# 20130725_Wave_Clock_PIC32MX130_Mono.net
KiCad netlist of a schematic drawn in EAGLE
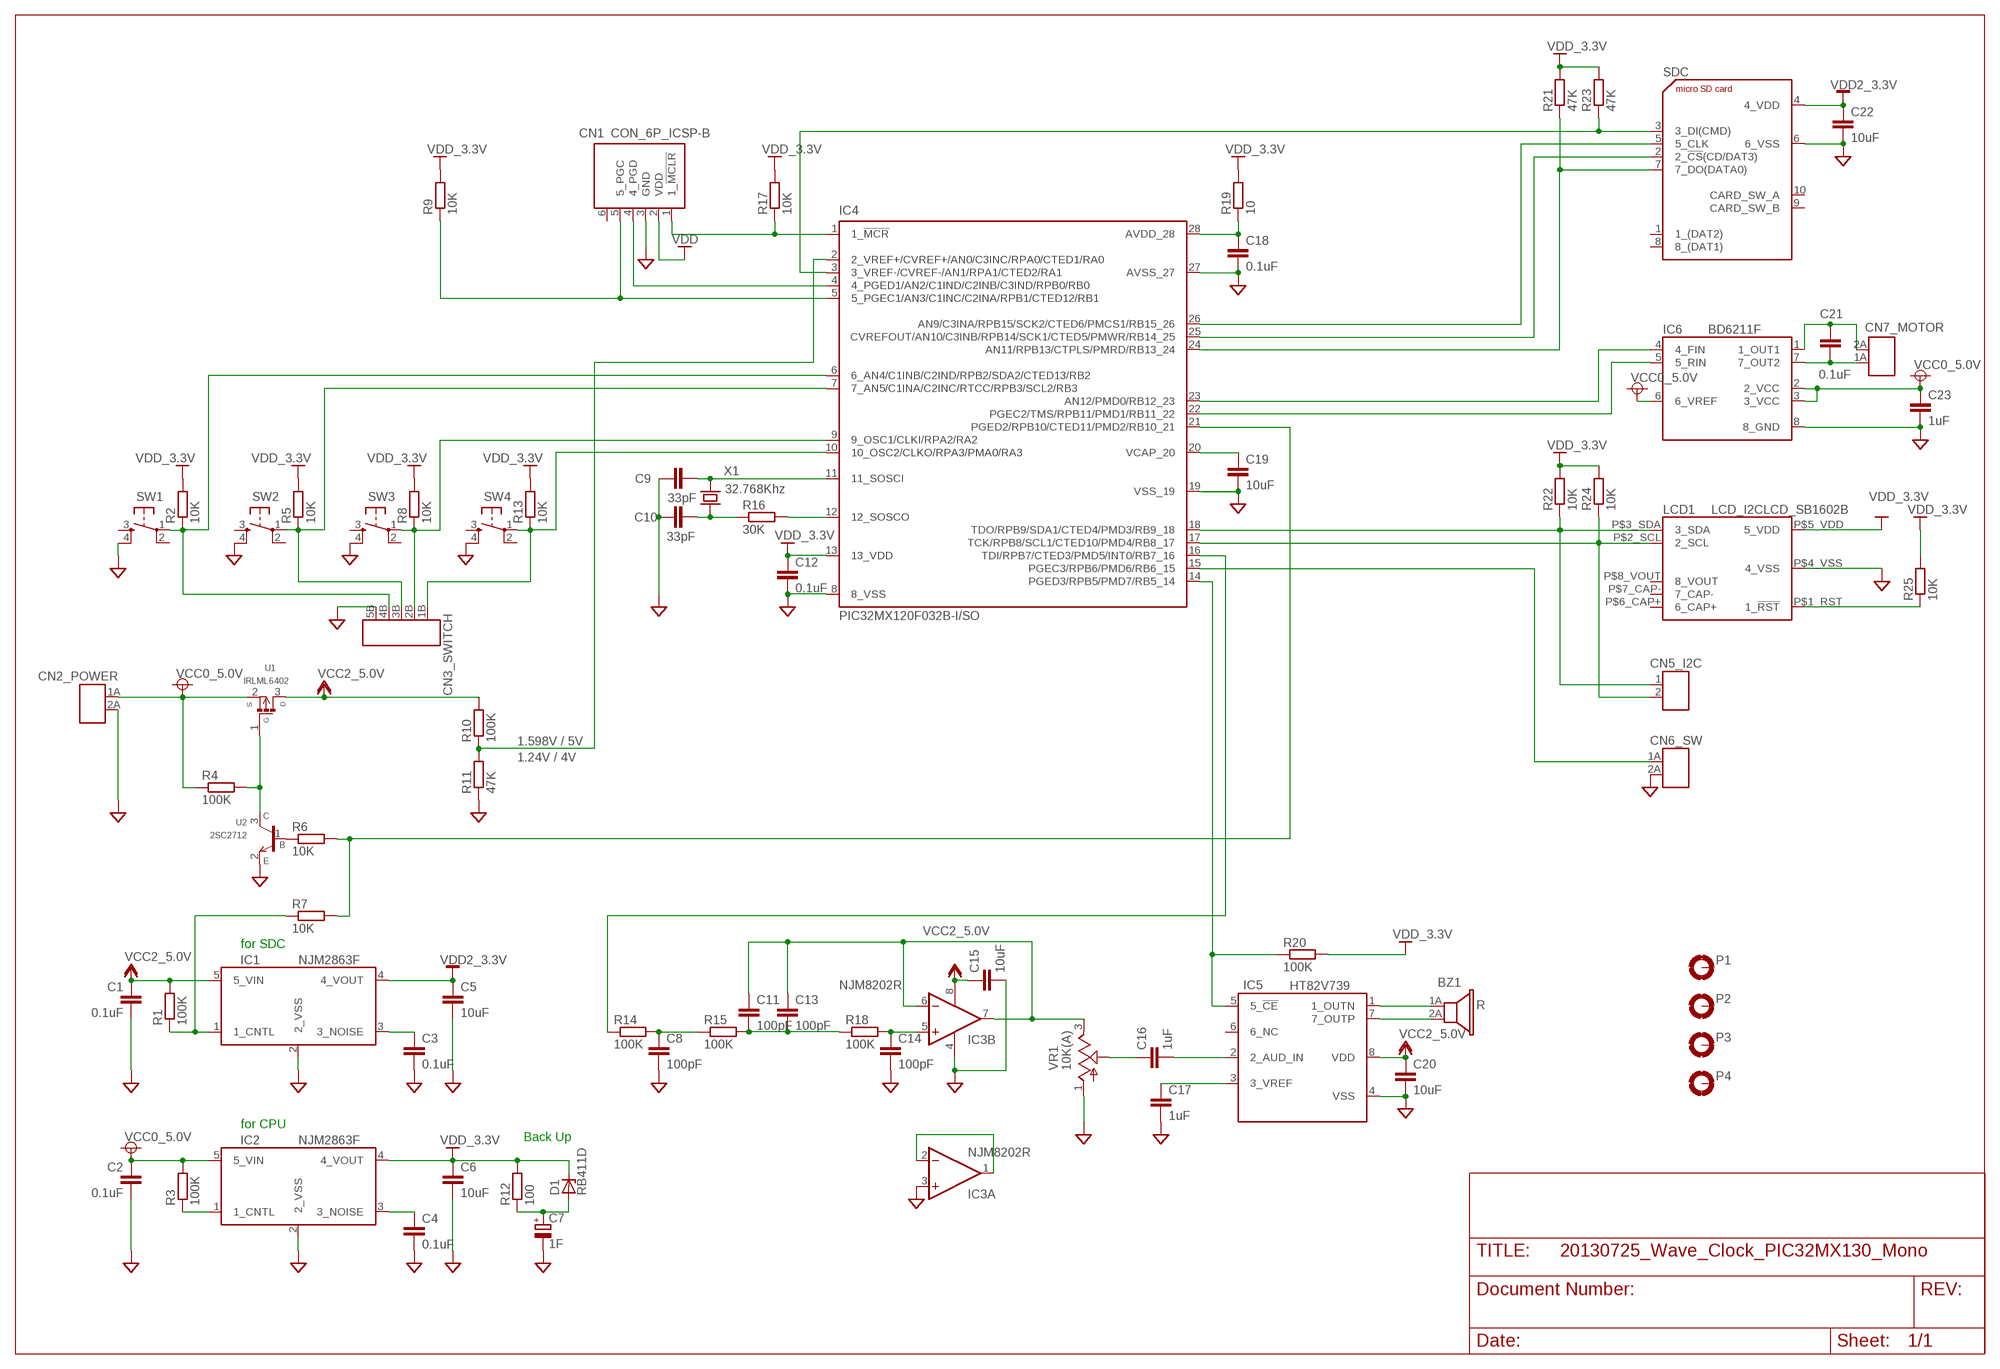
[diagram p0: schematic, sheet 1]

(export (version "E")
  (design (tool "Eeschema 10.0.6"))
  (components
    (comp (ref "BZ1")
      (value "R")
      (footprint "eagle-import:TERMINAL_AH-2P")
      (libsource (lib "eagle-import") (part "SPEAKER-H"))
    )
    (comp (ref "C1")
      (value "0.1uF")
      (footprint "eagle-import:1608")
      (libsource (lib "eagle-import") (part "C-EU2M1608"))
    )
    (comp (ref "C2")
      (value "0.1uF")
      (footprint "eagle-import:1608")
      (libsource (lib "eagle-import") (part "C-EU2M1608"))
    )
    (comp (ref "C3")
      (value "0.1uF")
      (footprint "eagle-import:1608")
      (libsource (lib "eagle-import") (part "C-EU2M1608"))
    )
    (comp (ref "C4")
      (value "0.1uF")
      (footprint "eagle-import:1608")
      (libsource (lib "eagle-import") (part "C-EU2M1608"))
    )
    (comp (ref "C5")
      (value "10uF")
      (footprint "eagle-import:3216")
      (libsource (lib "eagle-import") (part "C-EU2M3216"))
    )
    (comp (ref "C6")
      (value "10uF")
      (footprint "eagle-import:3216")
      (libsource (lib "eagle-import") (part "C-EU2M3216"))
    )
    (comp (ref "C7")
      (value "1F")
      (footprint "eagle-import:E5-19V-B")
      (libsource (lib "eagle-import") (part "CPOL-EDLC-1F5.5V-H"))
    )
    (comp (ref "C8")
      (value "100pF")
      (footprint "eagle-import:1608")
      (libsource (lib "eagle-import") (part "C-EU2M1608"))
    )
    (comp (ref "C9")
      (value "33pF")
      (footprint "eagle-import:1608")
      (libsource (lib "eagle-import") (part "C-EU2M1608"))
    )
    (comp (ref "C10")
      (value "33pF")
      (footprint "eagle-import:1608")
      (libsource (lib "eagle-import") (part "C-EU2M1608"))
    )
    (comp (ref "C11")
      (value "100pF")
      (footprint "eagle-import:1608")
      (libsource (lib "eagle-import") (part "C-EU2M1608"))
    )
    (comp (ref "C12")
      (value "0.1uF")
      (footprint "eagle-import:1608")
      (libsource (lib "eagle-import") (part "C-EU2M1608"))
    )
    (comp (ref "C13")
      (value "100pF")
      (footprint "eagle-import:1608")
      (libsource (lib "eagle-import") (part "C-EU2M1608"))
    )
    (comp (ref "C14")
      (value "100pF")
      (footprint "eagle-import:1608")
      (libsource (lib "eagle-import") (part "C-EU2M1608"))
    )
    (comp (ref "C15")
      (value "10uF")
      (footprint "eagle-import:3216")
      (libsource (lib "eagle-import") (part "C-EU2M3216"))
    )
    (comp (ref "C16")
      (value "1uF")
      (footprint "eagle-import:1608")
      (libsource (lib "eagle-import") (part "C-EU2M1608"))
    )
    (comp (ref "C17")
      (value "1uF")
      (footprint "eagle-import:1608")
      (libsource (lib "eagle-import") (part "C-EU2M1608"))
    )
    (comp (ref "C18")
      (value "0.1uF")
      (footprint "eagle-import:1608")
      (libsource (lib "eagle-import") (part "C-EU2M1608"))
    )
    (comp (ref "C19")
      (value "10uF")
      (footprint "eagle-import:3216")
      (libsource (lib "eagle-import") (part "C-EU2M3216"))
    )
    (comp (ref "C20")
      (value "10uF")
      (footprint "eagle-import:3216")
      (libsource (lib "eagle-import") (part "C-EU2M3216"))
    )
    (comp (ref "C21")
      (value "0.1uF")
      (footprint "eagle-import:1608")
      (libsource (lib "eagle-import") (part "C-EU2M1608"))
    )
    (comp (ref "C22")
      (value "10uF")
      (footprint "eagle-import:3216")
      (libsource (lib "eagle-import") (part "C-EU2M3216"))
    )
    (comp (ref "C23")
      (value "1uF")
      (footprint "eagle-import:1608")
      (libsource (lib "eagle-import") (part "C-EU2M1608"))
    )
    (comp (ref "CN1")
      (value "CON_6P_ICSP-B")
      (footprint "eagle-import:CON_DIP_6-B")
      (libsource (lib "eagle-import") (part "CON_6P_ICSP-B"))
    )
    (comp (ref "CN2_POWER")
      (value "CON_2P-B")
      (footprint "eagle-import:TERMINAL_AH-2P")
      (libsource (lib "eagle-import") (part "CON_2P-H"))
    )
    (comp (ref "CN3_SWITCH")
      (value "CON_5PVR")
      (footprint "eagle-import:TERMINAL_AV-5P")
      (libsource (lib "eagle-import") (part "CON_5PVR"))
    )
    (comp (ref "CN5_I2C")
      (value "CON_2P-B")
      (footprint "eagle-import:CON_DIP_2-B")
      (libsource (lib "eagle-import") (part "CON_2P-B"))
    )
    (comp (ref "CN6_SW")
      (value "CON_2P-B")
      (footprint "eagle-import:TERMINAL_AH-2P")
      (libsource (lib "eagle-import") (part "CON_2P-H"))
    )
    (comp (ref "CN7_MOTOR")
      (value "CON_2P-B")
      (footprint "eagle-import:TERMINAL_AH-2P")
      (libsource (lib "eagle-import") (part "CON_2P-H"))
    )
    (comp (ref "D1")
      (value "RB411D")
      (footprint "eagle-import:SOT-23-3-2915-B")
      (libsource (lib "eagle-import") (part "Z_DIODE-SC59"))
    )
    (comp (ref "IC1")
      (value "NJM2863F")
      (footprint "eagle-import:SOT-23-5-2916-B")
      (libsource (lib "eagle-import") (part "NJM2863F"))
    )
    (comp (ref "IC2")
      (value "NJM2863F")
      (footprint "eagle-import:SOT-23-5-2916-B")
      (libsource (lib "eagle-import") (part "NJM2863F"))
    )
    (comp (ref "IC3")
      (value "NJM8202R")
      (footprint "eagle-import:MSOP08")
      (libsource (lib "eagle-import") (part "NJM8202R"))
    )
    (comp (ref "IC4")
      (value "PIC32MX120F032B-I/SO")
      (footprint "eagle-import:SO28W")
      (libsource (lib "eagle-import") (part "PIC32MX120F032B-I/SO"))
    )
    (comp (ref "IC5")
      (value "HT82V739")
      (footprint "eagle-import:DIP08-B")
      (libsource (lib "eagle-import") (part "HT82V739"))
    )
    (comp (ref "IC6")
      (value "BD6211F")
      (footprint "eagle-import:SOP8")
      (libsource (lib "eagle-import") (part "BD6211F"))
    )
    (comp (ref "LCD1")
      (value "LCD_I2CLCD_SB1602B")
      (footprint "eagle-import:LCD_SB1602B")
      (libsource (lib "eagle-import") (part "LCD_I2CLCD_SB1602B"))
    )
    (comp (ref "P1")
      (value "MOUNT-PAD3.3")
      (footprint "eagle-import:PAD-3.3-B")
      (libsource (lib "eagle-import") (part "MOUNT-PAD3.3"))
    )
    (comp (ref "P2")
      (value "MOUNT-PAD3.3")
      (footprint "eagle-import:PAD-3.3-B")
      (libsource (lib "eagle-import") (part "MOUNT-PAD3.3"))
    )
    (comp (ref "P3")
      (value "MOUNT-PAD3.3")
      (footprint "eagle-import:PAD-3.3-B")
      (libsource (lib "eagle-import") (part "MOUNT-PAD3.3"))
    )
    (comp (ref "P4")
      (value "MOUNT-PAD3.3")
      (footprint "eagle-import:PAD-3.3-B")
      (libsource (lib "eagle-import") (part "MOUNT-PAD3.3"))
    )
    (comp (ref "R1")
      (value "100K")
      (footprint "eagle-import:1608")
      (libsource (lib "eagle-import") (part "R-EU2M1608"))
    )
    (comp (ref "R2")
      (value "10K")
      (footprint "eagle-import:1608")
      (libsource (lib "eagle-import") (part "R-EU2M1608"))
    )
    (comp (ref "R3")
      (value "100K")
      (footprint "eagle-import:1608")
      (libsource (lib "eagle-import") (part "R-EU2M1608"))
    )
    (comp (ref "R4")
      (value "100K")
      (footprint "eagle-import:1608")
      (libsource (lib "eagle-import") (part "R-EU2M1608"))
    )
    (comp (ref "R5")
      (value "10K")
      (footprint "eagle-import:1608")
      (libsource (lib "eagle-import") (part "R-EU2M1608"))
    )
    (comp (ref "R6")
      (value "10K")
      (footprint "eagle-import:1608")
      (libsource (lib "eagle-import") (part "R-EU2M1608"))
    )
    (comp (ref "R7")
      (value "10K")
      (footprint "eagle-import:1608")
      (libsource (lib "eagle-import") (part "R-EU2M1608"))
    )
    (comp (ref "R8")
      (value "10K")
      (footprint "eagle-import:1608")
      (libsource (lib "eagle-import") (part "R-EU2M1608"))
    )
    (comp (ref "R9")
      (value "10K")
      (footprint "eagle-import:1608")
      (libsource (lib "eagle-import") (part "R-EU2M1608"))
    )
    (comp (ref "R10")
      (value "100K")
      (footprint "eagle-import:1608")
      (libsource (lib "eagle-import") (part "R-EU2M1608"))
    )
    (comp (ref "R11")
      (value "47K")
      (footprint "eagle-import:1608")
      (libsource (lib "eagle-import") (part "R-EU2M1608"))
    )
    (comp (ref "R12")
      (value "100")
      (footprint "eagle-import:1608")
      (libsource (lib "eagle-import") (part "R-EU2M1608"))
    )
    (comp (ref "R13")
      (value "10K")
      (footprint "eagle-import:1608")
      (libsource (lib "eagle-import") (part "R-EU2M1608"))
    )
    (comp (ref "R14")
      (value "100K")
      (footprint "eagle-import:1608")
      (libsource (lib "eagle-import") (part "R-EU2M1608"))
    )
    (comp (ref "R15")
      (value "100K")
      (footprint "eagle-import:1608")
      (libsource (lib "eagle-import") (part "R-EU2M1608"))
    )
    (comp (ref "R16")
      (value "30K")
      (footprint "eagle-import:1608")
      (libsource (lib "eagle-import") (part "R-EU2M1608"))
    )
    (comp (ref "R17")
      (value "10K")
      (footprint "eagle-import:1608")
      (libsource (lib "eagle-import") (part "R-EU2M1608"))
    )
    (comp (ref "R18")
      (value "100K")
      (footprint "eagle-import:1608")
      (libsource (lib "eagle-import") (part "R-EU2M1608"))
    )
    (comp (ref "R19")
      (value "10")
      (footprint "eagle-import:1608")
      (libsource (lib "eagle-import") (part "R-EU2M1608"))
    )
    (comp (ref "R20")
      (value "100K")
      (footprint "eagle-import:1608")
      (libsource (lib "eagle-import") (part "R-EU2M1608"))
    )
    (comp (ref "R21")
      (value "47K")
      (footprint "eagle-import:1608")
      (libsource (lib "eagle-import") (part "R-EU2M1608"))
    )
    (comp (ref "R22")
      (value "10K")
      (footprint "eagle-import:1608")
      (libsource (lib "eagle-import") (part "R-EU2M1608"))
    )
    (comp (ref "R23")
      (value "47K")
      (footprint "eagle-import:1608")
      (libsource (lib "eagle-import") (part "R-EU2M1608"))
    )
    (comp (ref "R24")
      (value "10K")
      (footprint "eagle-import:1608")
      (libsource (lib "eagle-import") (part "R-EU2M1608"))
    )
    (comp (ref "R25")
      (value "10K")
      (footprint "eagle-import:1608")
      (libsource (lib "eagle-import") (part "R-EU2M1608"))
    )
    (comp (ref "SDC")
      (value "DM3AT-SF-PEJＤ")
      (footprint "eagle-import:DM3AT-SF-DIP")
      (libsource (lib "eagle-import") (part "DM3AT-SF-PEJＤ"))
    )
    (comp (ref "SW1")
      (value "SW_TACT1")
      (footprint "eagle-import:SW_TACT-B")
      (libsource (lib "eagle-import") (part "SW_TACT1"))
    )
    (comp (ref "SW2")
      (value "SW_TACT1")
      (footprint "eagle-import:SW_TACT-B")
      (libsource (lib "eagle-import") (part "SW_TACT1"))
    )
    (comp (ref "SW3")
      (value "SW_TACT1")
      (footprint "eagle-import:SW_TACT-B")
      (libsource (lib "eagle-import") (part "SW_TACT1"))
    )
    (comp (ref "SW4")
      (value "SW_TACT1")
      (footprint "eagle-import:SW_TACT-B")
      (libsource (lib "eagle-import") (part "SW_TACT1"))
    )
    (comp (ref "U1")
      (value "IRLML6402")
      (footprint "eagle-import:SC-59-2915")
      (libsource (lib "eagle-import") (part "IRLML6402"))
    )
    (comp (ref "U2")
      (value "2SC2712")
      (footprint "eagle-import:SOT-23-3-2915-B")
      (libsource (lib "eagle-import") (part "2SC2712"))
    )
    (comp (ref "VR1")
      (value "10K(A)")
      (footprint "eagle-import:VOL_MIDDLE")
      (libsource (lib "eagle-import") (part "POT-VOL"))
    )
    (comp (ref "X1")
      (value "32.768Khz")
      (footprint "eagle-import:VT-200")
      (libsource (lib "eagle-import") (part "XTALVT"))
    )
  )
  (nets
    (net (code "1") (name "GND") (class "Default")
      (node (ref "C1") (pin "2") (pinfunction "2_2") (pintype "passive"))
      (node (ref "C10") (pin "2") (pinfunction "2_2") (pintype "passive"))
      (node (ref "C12") (pin "2") (pinfunction "2_2") (pintype "passive"))
      (node (ref "C14") (pin "2") (pinfunction "2_2") (pintype "passive"))
      (node (ref "C15") (pin "2") (pinfunction "2_2") (pintype "passive"))
      (node (ref "C17") (pin "2") (pinfunction "2_2") (pintype "passive"))
      (node (ref "C18") (pin "2") (pinfunction "2_2") (pintype "passive"))
      (node (ref "C19") (pin "2") (pinfunction "2_2") (pintype "passive"))
      (node (ref "C2") (pin "2") (pinfunction "2_2") (pintype "passive"))
      (node (ref "C20") (pin "2") (pinfunction "2_2") (pintype "passive"))
      (node (ref "C22") (pin "2") (pinfunction "2_2") (pintype "passive"))
      (node (ref "C23") (pin "2") (pinfunction "2_2") (pintype "passive"))
      (node (ref "C3") (pin "2") (pinfunction "2_2") (pintype "passive"))
      (node (ref "C4") (pin "2") (pinfunction "2_2") (pintype "passive"))
      (node (ref "C5") (pin "2") (pinfunction "2_2") (pintype "passive"))
      (node (ref "C6") (pin "2") (pinfunction "2_2") (pintype "passive"))
      (node (ref "C7") (pin "-") (pinfunction "-_-") (pintype "passive"))
      (node (ref "C8") (pin "2") (pinfunction "2_2") (pintype "passive"))
      (node (ref "C9") (pin "2") (pinfunction "2_2") (pintype "passive"))
      (node (ref "CN1") (pin "3") (pinfunction "GND_3") (pintype "passive"))
      (node (ref "CN2_POWER") (pin "2A") (pinfunction "2_2A") (pintype "passive"))
      (node (ref "CN3_SWITCH") (pin "5B") (pinfunction "5_5B") (pintype "passive"))
      (node (ref "CN6_SW") (pin "2A") (pinfunction "2_2A") (pintype "passive"))
      (node (ref "IC1") (pin "2") (pinfunction "2_VSS_2") (pintype "power_in"))
      (node (ref "IC2") (pin "2") (pinfunction "2_VSS_2") (pintype "power_in"))
      (node (ref "IC3") (pin "3") (pinfunction "+IN_3") (pintype "input"))
      (node (ref "IC3") (pin "4") (pinfunction "V-_4") (pintype "power_in"))
      (node (ref "IC4") (pin "19") (pinfunction "VSS_19_19") (pintype "power_in"))
      (node (ref "IC4") (pin "27") (pinfunction "AVSS_27_27") (pintype "power_in"))
      (node (ref "IC4") (pin "8") (pinfunction "8_VSS_8") (pintype "power_in"))
      (node (ref "IC5") (pin "4") (pinfunction "VSS_4") (pintype "power_in"))
      (node (ref "IC6") (pin "8") (pinfunction "8_GND_8") (pintype "power_in"))
      (node (ref "LCD1") (pin "P$4_VSS") (pinfunction "4_VSS_P$4_VSS") (pintype "power_in"))
      (node (ref "R11") (pin "1") (pinfunction "1_1") (pintype "passive"))
      (node (ref "SDC") (pin "6") (pinfunction "6_VSS_6") (pintype "power_in"))
      (node (ref "SW1") (pin "4") (pinfunction "S1_4") (pintype "passive"))
      (node (ref "SW2") (pin "4") (pinfunction "S1_4") (pintype "passive"))
      (node (ref "SW3") (pin "4") (pinfunction "S1_4") (pintype "passive"))
      (node (ref "SW4") (pin "4") (pinfunction "S1_4") (pintype "passive"))
      (node (ref "U2") (pin "2") (pinfunction "E_2") (pintype "passive"))
      (node (ref "VR1") (pin "1") (pinfunction "A_1") (pintype "passive"))
    )
    (net (code "2") (name "Net-(BZ1-P$1)") (class "Default")
      (node (ref "BZ1") (pin "1A") (pinfunction "P$1_1A") (pintype "passive"))
      (node (ref "IC5") (pin "1") (pinfunction "1_OUTN_1") (pintype "output"))
    )
    (net (code "3") (name "Net-(BZ1-P$2)") (class "Default")
      (node (ref "BZ1") (pin "2A") (pinfunction "P$2_2A") (pintype "passive"))
      (node (ref "IC5") (pin "7") (pinfunction "7_OUTP_7") (pintype "output"))
    )
    (net (code "4") (name "Net-(C8-Pad1)") (class "Default")
      (node (ref "C8") (pin "1") (pinfunction "1_1") (pintype "passive"))
      (node (ref "R14") (pin "2") (pinfunction "2_2") (pintype "passive"))
      (node (ref "R15") (pin "1") (pinfunction "1_1") (pintype "passive"))
    )
    (net (code "5") (name "Net-(C11-Pad2)") (class "Default")
      (node (ref "C11") (pin "2") (pinfunction "2_2") (pintype "passive"))
      (node (ref "C13") (pin "2") (pinfunction "2_2") (pintype "passive"))
      (node (ref "R15") (pin "2") (pinfunction "2_2") (pintype "passive"))
      (node (ref "R18") (pin "1") (pinfunction "1_1") (pintype "passive"))
    )
    (net (code "6") (name "Net-(CN1-1_~{MCLR})") (class "Default")
      (node (ref "CN1") (pin "1") (pinfunction "1_~{MCLR}_1") (pintype "passive"))
      (node (ref "IC4") (pin "1") (pinfunction "1_~{MCR}_1") (pintype "input"))
      (node (ref "R17") (pin "1") (pinfunction "1_1") (pintype "passive"))
    )
    (net (code "7") (name "Net-(CN1-4_PGD)") (class "Default")
      (node (ref "CN1") (pin "4") (pinfunction "4_PGD_4") (pintype "passive"))
      (node (ref "IC4") (pin "4") (pinfunction "4_PGED1/AN2/C1IND/C2INB/C3IND/RPB0/RB0_4") (pintype "bidirectional"))
    )
    (net (code "8") (name "Net-(CN1-5_PGC)") (class "Default")
      (node (ref "CN1") (pin "5") (pinfunction "5_PGC_5") (pintype "passive"))
      (node (ref "IC4") (pin "5") (pinfunction "5_PGEC1/AN3/C1INC/C2INA/RPB1/CTED12/RB1_5") (pintype "bidirectional"))
      (node (ref "R9") (pin "1") (pinfunction "1_1") (pintype "passive"))
    )
    (net (code "9") (name "Net-(CN3_SWITCH-1)") (class "Default")
      (node (ref "CN3_SWITCH") (pin "1B") (pinfunction "1_1B") (pintype "passive"))
      (node (ref "IC4") (pin "10") (pinfunction "10_OSC2/CLKO/RPA3/PMA0/RA3_10") (pintype "bidirectional"))
      (node (ref "R13") (pin "1") (pinfunction "1_1") (pintype "passive"))
      (node (ref "SW4") (pin "1") (pinfunction "P_1") (pintype "passive"))
    )
    (net (code "10") (name "Net-(CN3_SWITCH-2)") (class "Default")
      (node (ref "CN3_SWITCH") (pin "2B") (pinfunction "2_2B") (pintype "passive"))
      (node (ref "IC4") (pin "9") (pinfunction "9_OSC1/CLKI/RPA2/RA2_9") (pintype "bidirectional"))
      (node (ref "R8") (pin "1") (pinfunction "1_1") (pintype "passive"))
      (node (ref "SW3") (pin "1") (pinfunction "P_1") (pintype "passive"))
    )
    (net (code "11") (name "Net-(CN3_SWITCH-3)") (class "Default")
      (node (ref "CN3_SWITCH") (pin "3B") (pinfunction "3_3B") (pintype "passive"))
      (node (ref "IC4") (pin "7") (pinfunction "7_AN5/C1INA/C2INC/RTCC/RPB3/SCL2/RB3_7") (pintype "bidirectional"))
      (node (ref "R5") (pin "1") (pinfunction "1_1") (pintype "passive"))
      (node (ref "SW2") (pin "1") (pinfunction "P_1") (pintype "passive"))
    )
    (net (code "12") (name "Net-(CN3_SWITCH-4)") (class "Default")
      (node (ref "CN3_SWITCH") (pin "4B") (pinfunction "4_4B") (pintype "passive"))
      (node (ref "IC4") (pin "6") (pinfunction "6_AN4/C1INB/C2IND/RPB2/SDA2/CTED13/RB2_6") (pintype "bidirectional"))
      (node (ref "R2") (pin "1") (pinfunction "1_1") (pintype "passive"))
      (node (ref "SW1") (pin "1") (pinfunction "P_1") (pintype "passive"))
    )
    (net (code "13") (name "Net-(CN6_SW-1)") (class "Default")
      (node (ref "CN6_SW") (pin "1A") (pinfunction "1_1A") (pintype "passive"))
      (node (ref "IC4") (pin "15") (pinfunction "PGEC3/RPB6/PMD6/RB6_15_15") (pintype "bidirectional"))
    )
    (net (code "14") (name "Net-(CN7_MOTOR-1)") (class "Default")
      (node (ref "C21") (pin "2") (pinfunction "2_2") (pintype "passive"))
      (node (ref "CN7_MOTOR") (pin "1A") (pinfunction "1_1A") (pintype "passive"))
      (node (ref "IC6") (pin "7") (pinfunction "7_OUT2_7") (pintype "output"))
    )
    (net (code "15") (name "Net-(CN7_MOTOR-2)") (class "Default")
      (node (ref "C21") (pin "1") (pinfunction "1_1") (pintype "passive"))
      (node (ref "CN7_MOTOR") (pin "2A") (pinfunction "2_2A") (pintype "passive"))
      (node (ref "IC6") (pin "1") (pinfunction "1_OUT1_1") (pintype "output"))
    )
    (net (code "16") (name "Net-(D1-A)") (class "Default")
      (node (ref "C7") (pin "+") (pinfunction "+_+") (pintype "passive"))
      (node (ref "D1") (pin "1") (pinfunction "A_1") (pintype "passive"))
      (node (ref "R12") (pin "1") (pinfunction "1_1") (pintype "passive"))
    )
    (net (code "17") (name "Net-(IC1-1_CNTL)") (class "Default")
      (node (ref "IC1") (pin "1") (pinfunction "1_CNTL_1") (pintype "input"))
      (node (ref "R1") (pin "1") (pinfunction "1_1") (pintype "passive"))
      (node (ref "R7") (pin "1") (pinfunction "1_1") (pintype "passive"))
    )
    (net (code "18") (name "Net-(IC1-3_NOISE)") (class "Default")
      (node (ref "C3") (pin "1") (pinfunction "1_1") (pintype "passive"))
      (node (ref "IC1") (pin "3") (pinfunction "3_NOISE_3") (pintype "passive"))
    )
    (net (code "19") (name "Net-(IC2-1_CNTL)") (class "Default")
      (node (ref "IC2") (pin "1") (pinfunction "1_CNTL_1") (pintype "input"))
      (node (ref "R3") (pin "1") (pinfunction "1_1") (pintype "passive"))
    )
    (net (code "20") (name "Net-(IC2-3_NOISE)") (class "Default")
      (node (ref "C4") (pin "1") (pinfunction "1_1") (pintype "passive"))
      (node (ref "IC2") (pin "3") (pinfunction "3_NOISE_3") (pintype "passive"))
    )
    (net (code "21") (name "Net-(IC3A--IN)") (class "Default")
      (node (ref "IC3") (pin "1") (pinfunction "OUT_1") (pintype "output"))
      (node (ref "IC3") (pin "2") (pinfunction "-IN_2") (pintype "input"))
    )
    (net (code "22") (name "Net-(IC3B-+IN)") (class "Default")
      (node (ref "C14") (pin "1") (pinfunction "1_1") (pintype "passive"))
      (node (ref "IC3") (pin "5") (pinfunction "+IN_5") (pintype "input"))
      (node (ref "R18") (pin "2") (pinfunction "2_2") (pintype "passive"))
    )
    (net (code "23") (name "Net-(IC3B--IN)") (class "Default")
      (node (ref "C11") (pin "1") (pinfunction "1_1") (pintype "passive"))
      (node (ref "C13") (pin "1") (pinfunction "1_1") (pintype "passive"))
      (node (ref "IC3") (pin "6") (pinfunction "-IN_6") (pintype "input"))
      (node (ref "IC3") (pin "7") (pinfunction "OUT_7") (pintype "output"))
      (node (ref "VR1") (pin "3") (pinfunction "E_3") (pintype "passive"))
    )
    (net (code "24") (name "Net-(IC4-2_VREF+{slash}CVREF+{slash}AN0{slash}C3INC{slash}RPA0{slash}CTED1{slash}RA0)") (class "Default")
      (node (ref "IC4") (pin "2") (pinfunction "2_VREF+/CVREF+/AN0/C3INC/RPA0/CTED1/RA0_2") (pintype "bidirectional"))
      (node (ref "R10") (pin "1") (pinfunction "1_1") (pintype "passive"))
      (node (ref "R11") (pin "2") (pinfunction "2_2") (pintype "passive"))
    )
    (net (code "25") (name "Net-(IC4-3_VREF-{slash}CVREF-{slash}AN1{slash}RPA1{slash}CTED2{slash}RA1)") (class "Default")
      (node (ref "IC4") (pin "3") (pinfunction "3_VREF-/CVREF-/AN1/RPA1/CTED2/RA1_3") (pintype "bidirectional"))
      (node (ref "R23") (pin "1") (pinfunction "1_1") (pintype "passive"))
      (node (ref "SDC") (pin "3") (pinfunction "3_DI(CMD)_3") (pintype "input"))
    )
    (net (code "26") (name "Net-(IC4-11_SOSCI)") (class "Default")
      (node (ref "C9") (pin "1") (pinfunction "1_1") (pintype "passive"))
      (node (ref "IC4") (pin "11") (pinfunction "11_SOSCI_11") (pintype "open_collector"))
      (node (ref "X1") (pin "P$2") (pinfunction "2_P$2") (pintype "passive"))
    )
    (net (code "27") (name "Net-(IC4-12_SOSCO)") (class "Default")
      (node (ref "IC4") (pin "12") (pinfunction "12_SOSCO_12") (pintype "open_collector"))
      (node (ref "R16") (pin "2") (pinfunction "2_2") (pintype "passive"))
    )
    (net (code "28") (name "Net-(IC4-AN9{slash}C3INA{slash}RPB15{slash}SCK2{slash}CTED6{slash}PMCS1{slash}RB15_26)") (class "Default")
      (node (ref "IC4") (pin "26") (pinfunction "AN9/C3INA/RPB15/SCK2/CTED6/PMCS1/RB15_26_26") (pintype "bidirectional"))
      (node (ref "SDC") (pin "5") (pinfunction "5_CLK_5") (pintype "input"))
    )
    (net (code "29") (name "Net-(IC4-AN11{slash}RPB13{slash}CTPLS{slash}PMRD{slash}RB13_24)") (class "Default")
      (node (ref "IC4") (pin "24") (pinfunction "AN11/RPB13/CTPLS/PMRD/RB13_24_24") (pintype "bidirectional"))
      (node (ref "R21") (pin "1") (pinfunction "1_1") (pintype "passive"))
      (node (ref "SDC") (pin "7") (pinfunction "7_DO(DATA0)_7") (pintype "output"))
    )
    (net (code "30") (name "Net-(IC4-AN12{slash}PMD0{slash}RB12_23)") (class "Default")
      (node (ref "IC4") (pin "23") (pinfunction "AN12/PMD0/RB12_23_23") (pintype "bidirectional"))
      (node (ref "IC6") (pin "4") (pinfunction "4_FIN_4") (pintype "input"))
    )
    (net (code "31") (name "Net-(IC4-AVDD_28)") (class "Default")
      (node (ref "C18") (pin "1") (pinfunction "1_1") (pintype "passive"))
      (node (ref "IC4") (pin "28") (pinfunction "AVDD_28_28") (pintype "passive"))
      (node (ref "R19") (pin "1") (pinfunction "1_1") (pintype "passive"))
    )
    (net (code "32") (name "Net-(IC4-CVREFOUT{slash}AN10{slash}C3INB{slash}RPB14{slash}SCK1{slash}CTED5{slash}PMWR{slash}RB14_25)") (class "Default")
      (node (ref "IC4") (pin "25") (pinfunction "CVREFOUT/AN10/C3INB/RPB14/SCK1/CTED5/PMWR/RB14_25_25") (pintype "bidirectional"))
      (node (ref "SDC") (pin "2") (pinfunction "2_~{CS}(CD/DAT3)_2") (pintype "input"))
    )
    (net (code "33") (name "Net-(IC4-PGEC2{slash}TMS{slash}RPB11{slash}PMD1{slash}RB11_22)") (class "Default")
      (node (ref "IC4") (pin "22") (pinfunction "PGEC2/TMS/RPB11/PMD1/RB11_22_22") (pintype "bidirectional"))
      (node (ref "IC6") (pin "5") (pinfunction "5_RIN_5") (pintype "input"))
    )
    (net (code "34") (name "Net-(IC4-PGED2{slash}RPB10{slash}CTED11{slash}PMD2{slash}RB10_21)") (class "Default")
      (node (ref "IC4") (pin "21") (pinfunction "PGED2/RPB10/CTED11/PMD2/RB10_21_21") (pintype "bidirectional"))
      (node (ref "R6") (pin "2") (pinfunction "2_2") (pintype "passive"))
      (node (ref "R7") (pin "2") (pinfunction "2_2") (pintype "passive"))
    )
    (net (code "35") (name "Net-(IC4-PGED3{slash}RPB5{slash}PMD7{slash}RB5_14)") (class "Default")
      (node (ref "IC4") (pin "14") (pinfunction "PGED3/RPB5/PMD7/RB5_14_14") (pintype "bidirectional"))
      (node (ref "IC5") (pin "5") (pinfunction "5_~{CE}_5") (pintype "input"))
      (node (ref "R20") (pin "1") (pinfunction "1_1") (pintype "passive"))
    )
    (net (code "36") (name "Net-(IC4-TCK{slash}RPB8{slash}SCL1{slash}CTED10{slash}PMD4{slash}RB8_17)") (class "Default")
      (node (ref "CN5_I2C") (pin "2") (pinfunction "2_2") (pintype "passive"))
      (node (ref "IC4") (pin "17") (pinfunction "TCK/RPB8/SCL1/CTED10/PMD4/RB8_17_17") (pintype "bidirectional"))
      (node (ref "LCD1") (pin "P$2_SCL") (pinfunction "2_SCL_P$2_SCL") (pintype "passive"))
      (node (ref "R24") (pin "1") (pinfunction "1_1") (pintype "passive"))
    )
    (net (code "37") (name "Net-(IC4-TDI{slash}RPB7{slash}CTED3{slash}PMD5{slash}INT0{slash}RB7_16)") (class "Default")
      (node (ref "IC4") (pin "16") (pinfunction "TDI/RPB7/CTED3/PMD5/INT0/RB7_16_16") (pintype "bidirectional"))
      (node (ref "R14") (pin "1") (pinfunction "1_1") (pintype "passive"))
    )
    (net (code "38") (name "Net-(IC4-TDO{slash}RPB9{slash}SDA1{slash}CTED4{slash}PMD3{slash}RB9_18)") (class "Default")
      (node (ref "CN5_I2C") (pin "1") (pinfunction "1_1") (pintype "passive"))
      (node (ref "IC4") (pin "18") (pinfunction "TDO/RPB9/SDA1/CTED4/PMD3/RB9_18_18") (pintype "bidirectional"))
      (node (ref "LCD1") (pin "P$3_SDA") (pinfunction "3_SDA_P$3_SDA") (pintype "passive"))
      (node (ref "R22") (pin "1") (pinfunction "1_1") (pintype "passive"))
    )
    (net (code "39") (name "Net-(IC4-VCAP_20)") (class "Default")
      (node (ref "C19") (pin "1") (pinfunction "1_1") (pintype "passive"))
      (node (ref "IC4") (pin "20") (pinfunction "VCAP_20_20") (pintype "passive"))
    )
    (net (code "40") (name "Net-(IC5-2_AUD_IN)") (class "Default")
      (node (ref "C16") (pin "2") (pinfunction "2_2") (pintype "passive"))
      (node (ref "IC5") (pin "2") (pinfunction "2_AUD_IN_2") (pintype "input"))
    )
    (net (code "41") (name "Net-(IC5-3_VREF)") (class "Default")
      (node (ref "C17") (pin "1") (pinfunction "1_1") (pintype "passive"))
      (node (ref "IC5") (pin "3") (pinfunction "3_VREF_3") (pintype "passive"))
    )
    (net (code "42") (name "Net-(LCD1-1_~{RST})") (class "Default")
      (node (ref "LCD1") (pin "P$1_RST") (pinfunction "1_~{RST}_P$1_RST") (pintype "passive"))
      (node (ref "R25") (pin "1") (pinfunction "1_1") (pintype "passive"))
    )
    (net (code "43") (name "Net-(U1-G)") (class "Default")
      (node (ref "R4") (pin "2") (pinfunction "2_2") (pintype "passive"))
      (node (ref "U1") (pin "1") (pinfunction "G_1") (pintype "passive"))
      (node (ref "U2") (pin "3") (pinfunction "C_3") (pintype "passive"))
    )
    (net (code "44") (name "Net-(U2-B)") (class "Default")
      (node (ref "R6") (pin "1") (pinfunction "1_1") (pintype "passive"))
      (node (ref "U2") (pin "1") (pinfunction "B_1") (pintype "passive"))
    )
    (net (code "45") (name "Net-(VR1-S)") (class "Default")
      (node (ref "C16") (pin "1") (pinfunction "1_1") (pintype "passive"))
      (node (ref "VR1") (pin "2") (pinfunction "S_2") (pintype "passive"))
    )
    (net (code "46") (name "Net-(X1-1)") (class "Default")
      (node (ref "C10") (pin "1") (pinfunction "1_1") (pintype "passive"))
      (node (ref "R16") (pin "1") (pinfunction "1_1") (pintype "passive"))
      (node (ref "X1") (pin "P$1") (pinfunction "1_P$1") (pintype "passive"))
    )
    (net (code "47") (name "VCC0_5.0V") (class "Default")
      (node (ref "C2") (pin "1") (pinfunction "1_1") (pintype "passive"))
      (node (ref "C23") (pin "1") (pinfunction "1_1") (pintype "passive"))
      (node (ref "CN2_POWER") (pin "1A") (pinfunction "1_1A") (pintype "passive"))
      (node (ref "IC2") (pin "5") (pinfunction "5_VIN_5") (pintype "power_in"))
      (node (ref "IC6") (pin "2") (pinfunction "2_VCC_2") (pintype "power_in"))
      (node (ref "IC6") (pin "3") (pinfunction "3_VCC_3") (pintype "power_in"))
      (node (ref "IC6") (pin "6") (pinfunction "6_VREF_6") (pintype "passive"))
      (node (ref "R3") (pin "2") (pinfunction "2_2") (pintype "passive"))
      (node (ref "R4") (pin "1") (pinfunction "1_1") (pintype "passive"))
      (node (ref "U1") (pin "2") (pinfunction "S_2") (pintype "passive"))
    )
    (net (code "48") (name "VCC2_5.0V") (class "Default")
      (node (ref "C1") (pin "1") (pinfunction "1_1") (pintype "passive"))
      (node (ref "C15") (pin "1") (pinfunction "1_1") (pintype "passive"))
      (node (ref "C20") (pin "1") (pinfunction "1_1") (pintype "passive"))
      (node (ref "IC1") (pin "5") (pinfunction "5_VIN_5") (pintype "power_in"))
      (node (ref "IC3") (pin "8") (pinfunction "V+_8") (pintype "power_in"))
      (node (ref "IC5") (pin "8") (pinfunction "VDD_8") (pintype "power_in"))
      (node (ref "R1") (pin "2") (pinfunction "2_2") (pintype "passive"))
      (node (ref "R10") (pin "2") (pinfunction "2_2") (pintype "passive"))
      (node (ref "U1") (pin "3") (pinfunction "D_3") (pintype "passive"))
    )
    (net (code "49") (name "VDD") (class "Default")
      (node (ref "C12") (pin "1") (pinfunction "1_1") (pintype "passive"))
      (node (ref "C6") (pin "1") (pinfunction "1_1") (pintype "passive"))
      (node (ref "CN1") (pin "2") (pinfunction "VDD_2") (pintype "passive"))
      (node (ref "D1") (pin "3") (pinfunction "C_3") (pintype "passive"))
      (node (ref "IC2") (pin "4") (pinfunction "4_VOUT_4") (pintype "power_in"))
      (node (ref "IC4") (pin "13") (pinfunction "13_VDD_13") (pintype "power_in"))
      (node (ref "LCD1") (pin "P$5_VDD") (pinfunction "5_VDD_P$5_VDD") (pintype "power_in"))
      (node (ref "R12") (pin "2") (pinfunction "2_2") (pintype "passive"))
      (node (ref "R13") (pin "2") (pinfunction "2_2") (pintype "passive"))
      (node (ref "R17") (pin "2") (pinfunction "2_2") (pintype "passive"))
      (node (ref "R19") (pin "2") (pinfunction "2_2") (pintype "passive"))
      (node (ref "R2") (pin "2") (pinfunction "2_2") (pintype "passive"))
      (node (ref "R20") (pin "2") (pinfunction "2_2") (pintype "passive"))
      (node (ref "R21") (pin "2") (pinfunction "2_2") (pintype "passive"))
      (node (ref "R22") (pin "2") (pinfunction "2_2") (pintype "passive"))
      (node (ref "R23") (pin "2") (pinfunction "2_2") (pintype "passive"))
      (node (ref "R24") (pin "2") (pinfunction "2_2") (pintype "passive"))
      (node (ref "R25") (pin "2") (pinfunction "2_2") (pintype "passive"))
      (node (ref "R5") (pin "2") (pinfunction "2_2") (pintype "passive"))
      (node (ref "R8") (pin "2") (pinfunction "2_2") (pintype "passive"))
      (node (ref "R9") (pin "2") (pinfunction "2_2") (pintype "passive"))
    )
    (net (code "50") (name "VDD2_3.3V") (class "Default")
      (node (ref "C22") (pin "1") (pinfunction "1_1") (pintype "passive"))
      (node (ref "C5") (pin "1") (pinfunction "1_1") (pintype "passive"))
      (node (ref "IC1") (pin "4") (pinfunction "4_VOUT_4") (pintype "power_in"))
      (node (ref "SDC") (pin "4") (pinfunction "4_VDD_4") (pintype "power_in"))
    )
    (net (code "51") (name "unconnected-(CN1-Pad6)") (class "Default")
      (node (ref "CN1") (pin "6") (pinfunction "6_6") (pintype "passive"))
    )
    (net (code "52") (name "unconnected-(IC5-6_NC-Pad6)") (class "Default")
      (node (ref "IC5") (pin "6") (pinfunction "6_NC_6") (pintype "no_connect"))
    )
    (net (code "53") (name "unconnected-(LCD1-6_CAP+-PadP$6_CAP+)") (class "Default")
      (node (ref "LCD1") (pin "P$6_CAP+") (pinfunction "6_CAP+_P$6_CAP+") (pintype "passive"))
    )
    (net (code "54") (name "unconnected-(LCD1-7_CAP--PadP$7_CAP-)") (class "Default")
      (node (ref "LCD1") (pin "P$7_CAP-") (pinfunction "7_CAP-_P$7_CAP-") (pintype "passive"))
    )
    (net (code "55") (name "unconnected-(LCD1-8_VOUT-PadP$8_VOUT)") (class "Default")
      (node (ref "LCD1") (pin "P$8_VOUT") (pinfunction "8_VOUT_P$8_VOUT") (pintype "passive"))
    )
    (net (code "56") (name "unconnected-(P1-MOUNT-PadB2,1)") (class "Default")
      (node (ref "P1") (pin "B2,1") (pinfunction "MOUNT_B2,1") (pintype "passive"))
    )
    (net (code "57") (name "unconnected-(P2-MOUNT-PadB2,1)") (class "Default")
      (node (ref "P2") (pin "B2,1") (pinfunction "MOUNT_B2,1") (pintype "passive"))
    )
    (net (code "58") (name "unconnected-(P3-MOUNT-PadB2,1)") (class "Default")
      (node (ref "P3") (pin "B2,1") (pinfunction "MOUNT_B2,1") (pintype "passive"))
    )
    (net (code "59") (name "unconnected-(P4-MOUNT-PadB2,1)") (class "Default")
      (node (ref "P4") (pin "B2,1") (pinfunction "MOUNT_B2,1") (pintype "passive"))
    )
    (net (code "60") (name "unconnected-(SDC-1_(DAT2)-Pad1)") (class "Default")
      (node (ref "SDC") (pin "1") (pinfunction "1_(DAT2)_1") (pintype "no_connect"))
    )
    (net (code "61") (name "unconnected-(SDC-8_(DAT1)-Pad8)") (class "Default")
      (node (ref "SDC") (pin "8") (pinfunction "8_(DAT1)_8") (pintype "no_connect"))
    )
    (net (code "62") (name "unconnected-(SDC-CARD_SW_A-Pad10)") (class "Default")
      (node (ref "SDC") (pin "10") (pinfunction "CARD_SW_A_10") (pintype "bidirectional"))
    )
    (net (code "63") (name "unconnected-(SDC-CARD_SW_B-Pad9)") (class "Default")
      (node (ref "SDC") (pin "9") (pinfunction "CARD_SW_B_9") (pintype "bidirectional"))
    )
    (net (code "64") (name "unconnected-(SW1-P1-Pad2)") (class "Default")
      (node (ref "SW1") (pin "2") (pinfunction "P1_2") (pintype "passive"))
    )
    (net (code "65") (name "unconnected-(SW1-S-Pad3)") (class "Default")
      (node (ref "SW1") (pin "3") (pinfunction "S_3") (pintype "passive"))
    )
    (net (code "66") (name "unconnected-(SW2-P1-Pad2)") (class "Default")
      (node (ref "SW2") (pin "2") (pinfunction "P1_2") (pintype "passive"))
    )
    (net (code "67") (name "unconnected-(SW2-S-Pad3)") (class "Default")
      (node (ref "SW2") (pin "3") (pinfunction "S_3") (pintype "passive"))
    )
    (net (code "68") (name "unconnected-(SW3-P1-Pad2)") (class "Default")
      (node (ref "SW3") (pin "2") (pinfunction "P1_2") (pintype "passive"))
    )
    (net (code "69") (name "unconnected-(SW3-S-Pad3)") (class "Default")
      (node (ref "SW3") (pin "3") (pinfunction "S_3") (pintype "passive"))
    )
    (net (code "70") (name "unconnected-(SW4-P1-Pad2)") (class "Default")
      (node (ref "SW4") (pin "2") (pinfunction "P1_2") (pintype "passive"))
    )
    (net (code "71") (name "unconnected-(SW4-S-Pad3)") (class "Default")
      (node (ref "SW4") (pin "3") (pinfunction "S_3") (pintype "passive"))
    )
  )
)
